# Scheme.net
KiCad netlist of a schematic drawn in Altium Designer
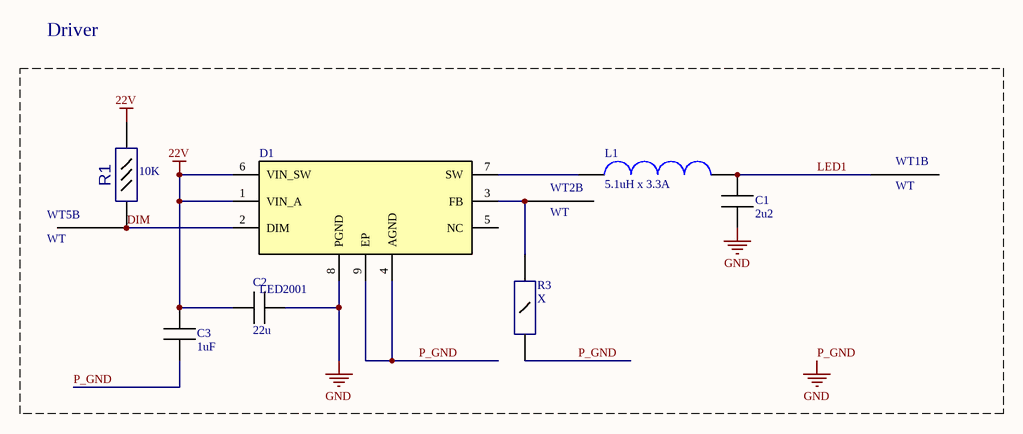
[diagram p0: Scheme.SchDoc]

(export (version "E")
  (design (tool "Eeschema 10.0.6"))
  (components
    (comp (ref "C1")
      (value "2u2")
      (footprint "Cap 0603")
      (description "C 2.2uF  x 25V")
      (fields (field (name "VOLTAGE") "25V"))
      (libsource (lib "Altium Vault") (part "Capasitor Ceramic"))
    )
    (comp (ref "C2")
      (value "22u")
      (footprint "Cap 1206")
      (description "C 22uF x 25V")
      (fields (field (name "VOLTAGE") "25V"))
      (libsource (lib "Altium Vault") (part "Capasitor Ceramic"))
    )
    (comp (ref "C3")
      (value "1uF")
      (footprint "Cap 0603")
      (description "C 1uF  x 25V")
      (fields (field (name "VOLTAGE") "25V") (field (name "Comment") "1u0"))
      (libsource (lib "Altium Vault") (part "Capasitor Ceramic"))
    )
    (comp (ref "D1")
      (value "LED2001")
      (footprint "VQFPN-8 4x4")
      (libsource (lib "Altium Vault") (part "CMP-00546-6"))
    )
    (comp (ref "L1")
      (value "5.1uH x 3.3A")
      (footprint "ASPI-6045S-5R1N-T")
      (description "ASPI-6045S-5R1N-T, 5.1uH x 3.3A")
      (fields (field (name "Comment") "51"))
      (libsource (lib "Altium Vault") (part "CMP-00554-1"))
    )
    (comp (ref "R1")
      (value "10K")
      (footprint "R0603 5%")
      (description "R 10K")
      (fields (field (name "Comment") "103"))
      (libsource (lib "Altium Vault") (part "CMP-00052-2"))
    )
    (comp (ref "R3")
      (value "X")
      (footprint "Resistor 1206")
      (description "R X")
      (libsource (lib "Altium Vault") (part "R1206"))
    )
    (comp (ref "WT1") (value "WT") (footprint "WT") (libsource (lib "Altium Vault") (part "WireTerminal")))
    (comp (ref "WT2") (value "WT") (footprint "WT") (libsource (lib "") (part "CMP-00159-1_1")))
    (comp (ref "WT5") (value "WT") (footprint "WT") (libsource (lib "Altium Vault") (part "CMP-00159-1")))
  )
  (nets
    (net (code "1") (name "/DIM") (class "Default")
      (node (ref "D1") (pin "2") (pinfunction "DIM_2") (pintype "passive"))
      (node (ref "R1") (pin "1") (pinfunction "1_1") (pintype "passive"))
      (node (ref "WT5") (pin "1") (pinfunction "1_1") (pintype "passive"))
    )
    (net (code "2") (name "/LED1") (class "Default")
      (node (ref "C1") (pin "2") (pinfunction "2_2") (pintype "passive"))
      (node (ref "L1") (pin "2") (pinfunction "2_2") (pintype "passive"))
      (node (ref "WT1") (pin "1") (pinfunction "1_1") (pintype "passive"))
    )
    (net (code "3") (name "22V") (class "Default")
      (node (ref "C2") (pin "1") (pinfunction "1_1") (pintype "passive"))
      (node (ref "C3") (pin "2") (pinfunction "2_2") (pintype "passive"))
      (node (ref "D1") (pin "1") (pinfunction "VIN_A_1") (pintype "passive"))
      (node (ref "D1") (pin "6") (pinfunction "VIN_SW_6") (pintype "passive"))
      (node (ref "R1") (pin "2") (pinfunction "2_2") (pintype "passive"))
    )
    (net (code "4") (name "GND") (class "Default")
      (node (ref "C1") (pin "1") (pinfunction "1_1") (pintype "passive"))
      (node (ref "C2") (pin "2") (pinfunction "2_2") (pintype "passive"))
      (node (ref "C3") (pin "1") (pinfunction "1_1") (pintype "passive"))
      (node (ref "D1") (pin "4") (pinfunction "AGND_4") (pintype "passive"))
      (node (ref "D1") (pin "8") (pinfunction "PGND_8") (pintype "passive"))
      (node (ref "D1") (pin "9") (pinfunction "EP_9") (pintype "passive"))
      (node (ref "R3") (pin "1") (pinfunction "1_1") (pintype "passive"))
    )
    (net (code "5") (name "Net-(D1-FB)") (class "Default")
      (node (ref "D1") (pin "3") (pinfunction "FB_3") (pintype "passive"))
      (node (ref "R3") (pin "2") (pinfunction "2_2") (pintype "passive"))
      (node (ref "WT2") (pin "1") (pinfunction "1_1") (pintype "passive"))
    )
    (net (code "6") (name "Net-(D1-SW)") (class "Default")
      (node (ref "D1") (pin "7") (pinfunction "SW_7") (pintype "passive"))
      (node (ref "L1") (pin "1") (pinfunction "1_1") (pintype "passive"))
    )
    (net (code "7") (name "unconnected-(D1-NC-Pad5)") (class "Default")
      (node (ref "D1") (pin "5") (pinfunction "NC_5") (pintype "passive"))
    )
  )
)
